# CPU.net
KiCad netlist of a schematic drawn in EAGLE
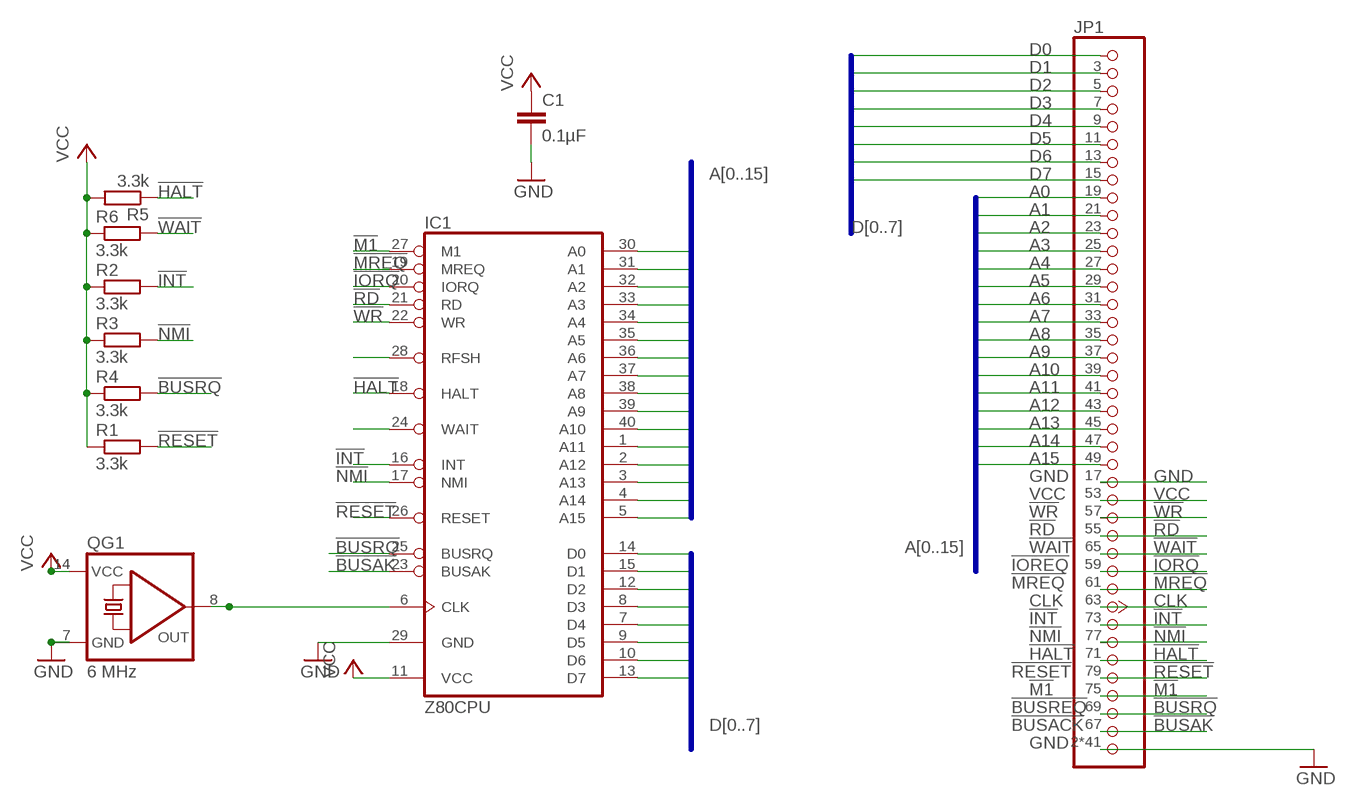
[diagram p0: schematic, sheet 1]

(export (version "E")
  (design (tool "Eeschema 10.0.6"))
  (components
    (comp (ref "C1")
      (value "0.1µF")
      (footprint "eagle-import:C5B2.5")
      (libsource (lib "eagle-import") (part "C5/2.5"))
    )
    (comp (ref "IC1")
      (value "Z80CPU")
      (footprint "eagle-import:DIL40")
      (libsource (lib "eagle-import") (part "Z80CPU"))
    )
    (comp (ref "JP1")
      (value "JEANNECTOR/90")
      (footprint "eagle-import:2X25_90")
      (libsource (lib "eagle-import") (part "JEANNECTOR/90"))
    )
    (comp (ref "QG1")
      (value "6 MHz")
      (footprint "eagle-import:DIL14S")
      (libsource (lib "eagle-import") (part "QG5860"))
    )
    (comp (ref "R1")
      (value "3.3k")
      (footprint "eagle-import:0207_2V")
      (libsource (lib "eagle-import") (part "R-EU_0207/2V"))
    )
    (comp (ref "R2")
      (value "3.3k")
      (footprint "eagle-import:0207_2V")
      (libsource (lib "eagle-import") (part "R-EU_0207/2V"))
    )
    (comp (ref "R3")
      (value "3.3k")
      (footprint "eagle-import:0207_2V")
      (libsource (lib "eagle-import") (part "R-EU_0207/2V"))
    )
    (comp (ref "R4")
      (value "3.3k")
      (footprint "eagle-import:0207_2V")
      (libsource (lib "eagle-import") (part "R-EU_0207/2V"))
    )
    (comp (ref "R5")
      (value "3.3k")
      (footprint "eagle-import:0207_2V")
      (libsource (lib "eagle-import") (part "R-EU_0207/2V"))
    )
    (comp (ref "R6")
      (value "3.3k")
      (footprint "eagle-import:0207_2V")
      (libsource (lib "eagle-import") (part "R-EU_0207/2V"))
    )
  )
  (nets
    (net (code "1") (name "/A0") (class "Default")
      (node (ref "IC1") (pin "30") (pinfunction "A0_30") (pintype "output"))
      (node (ref "JP1") (pin "19") (pinfunction "A0_19") (pintype "bidirectional"))
    )
    (net (code "2") (name "/A1") (class "Default")
      (node (ref "IC1") (pin "31") (pinfunction "A1_31") (pintype "output"))
      (node (ref "JP1") (pin "21") (pinfunction "A1_21") (pintype "bidirectional"))
    )
    (net (code "3") (name "/A2") (class "Default")
      (node (ref "IC1") (pin "32") (pinfunction "A2_32") (pintype "output"))
      (node (ref "JP1") (pin "23") (pinfunction "A2_23") (pintype "bidirectional"))
    )
    (net (code "4") (name "/A3") (class "Default")
      (node (ref "IC1") (pin "33") (pinfunction "A3_33") (pintype "output"))
      (node (ref "JP1") (pin "25") (pinfunction "A3_25") (pintype "bidirectional"))
    )
    (net (code "5") (name "/A4") (class "Default")
      (node (ref "IC1") (pin "34") (pinfunction "A4_34") (pintype "output"))
      (node (ref "JP1") (pin "27") (pinfunction "A4_27") (pintype "bidirectional"))
    )
    (net (code "6") (name "/A5") (class "Default")
      (node (ref "IC1") (pin "35") (pinfunction "A5_35") (pintype "output"))
      (node (ref "JP1") (pin "29") (pinfunction "A5_29") (pintype "bidirectional"))
    )
    (net (code "7") (name "/A6") (class "Default")
      (node (ref "IC1") (pin "36") (pinfunction "A6_36") (pintype "output"))
      (node (ref "JP1") (pin "31") (pinfunction "A6_31") (pintype "bidirectional"))
    )
    (net (code "8") (name "/A7") (class "Default")
      (node (ref "IC1") (pin "37") (pinfunction "A7_37") (pintype "output"))
      (node (ref "JP1") (pin "33") (pinfunction "A7_33") (pintype "bidirectional"))
    )
    (net (code "9") (name "/A8") (class "Default")
      (node (ref "IC1") (pin "38") (pinfunction "A8_38") (pintype "output"))
      (node (ref "JP1") (pin "35") (pinfunction "A8_35") (pintype "bidirectional"))
    )
    (net (code "10") (name "/A9") (class "Default")
      (node (ref "IC1") (pin "39") (pinfunction "A9_39") (pintype "output"))
      (node (ref "JP1") (pin "37") (pinfunction "A9_37") (pintype "bidirectional"))
    )
    (net (code "11") (name "/A10") (class "Default")
      (node (ref "IC1") (pin "40") (pinfunction "A10_40") (pintype "output"))
      (node (ref "JP1") (pin "39") (pinfunction "A10_39") (pintype "bidirectional"))
    )
    (net (code "12") (name "/A11") (class "Default")
      (node (ref "IC1") (pin "1") (pinfunction "A11_1") (pintype "output"))
      (node (ref "JP1") (pin "41") (pinfunction "A11_41") (pintype "bidirectional"))
    )
    (net (code "13") (name "/A12") (class "Default")
      (node (ref "IC1") (pin "2") (pinfunction "A12_2") (pintype "output"))
      (node (ref "JP1") (pin "43") (pinfunction "A12_43") (pintype "bidirectional"))
    )
    (net (code "14") (name "/A13") (class "Default")
      (node (ref "IC1") (pin "3") (pinfunction "A13_3") (pintype "output"))
      (node (ref "JP1") (pin "45") (pinfunction "A13_45") (pintype "bidirectional"))
    )
    (net (code "15") (name "/A14") (class "Default")
      (node (ref "IC1") (pin "4") (pinfunction "A14_4") (pintype "output"))
      (node (ref "JP1") (pin "47") (pinfunction "A14_47") (pintype "bidirectional"))
    )
    (net (code "16") (name "/A15") (class "Default")
      (node (ref "IC1") (pin "5") (pinfunction "A15_5") (pintype "output"))
      (node (ref "JP1") (pin "49") (pinfunction "A15_49") (pintype "bidirectional"))
    )
    (net (code "18") (name "/CLK") (class "Default")
      (node (ref "IC1") (pin "6") (pinfunction "CLK_6") (pintype "input"))
      (node (ref "JP1") (pin "63") (pinfunction "CLK_63") (pintype "passive"))
      (node (ref "QG1") (pin "8") (pinfunction "OUT_8") (pintype "output"))
    )
    (net (code "19") (name "/D0") (class "Default")
      (node (ref "IC1") (pin "14") (pinfunction "D0_14") (pintype "bidirectional"))
      (node (ref "JP1") (pin "1") (pinfunction "D0_1") (pintype "bidirectional"))
    )
    (net (code "20") (name "/D1") (class "Default")
      (node (ref "IC1") (pin "15") (pinfunction "D1_15") (pintype "bidirectional"))
      (node (ref "JP1") (pin "3") (pinfunction "D1_3") (pintype "bidirectional"))
    )
    (net (code "21") (name "/D2") (class "Default")
      (node (ref "IC1") (pin "12") (pinfunction "D2_12") (pintype "bidirectional"))
      (node (ref "JP1") (pin "5") (pinfunction "D2_5") (pintype "bidirectional"))
    )
    (net (code "22") (name "/D3") (class "Default")
      (node (ref "IC1") (pin "8") (pinfunction "D3_8") (pintype "bidirectional"))
      (node (ref "JP1") (pin "7") (pinfunction "D3_7") (pintype "bidirectional"))
    )
    (net (code "23") (name "/D4") (class "Default")
      (node (ref "IC1") (pin "7") (pinfunction "D4_7") (pintype "bidirectional"))
      (node (ref "JP1") (pin "9") (pinfunction "D4_9") (pintype "bidirectional"))
    )
    (net (code "24") (name "/D5") (class "Default")
      (node (ref "IC1") (pin "9") (pinfunction "D5_9") (pintype "bidirectional"))
      (node (ref "JP1") (pin "11") (pinfunction "D5_11") (pintype "bidirectional"))
    )
    (net (code "25") (name "/D6") (class "Default")
      (node (ref "IC1") (pin "10") (pinfunction "D6_10") (pintype "bidirectional"))
      (node (ref "JP1") (pin "13") (pinfunction "D6_13") (pintype "bidirectional"))
    )
    (net (code "26") (name "/D7") (class "Default")
      (node (ref "IC1") (pin "13") (pinfunction "D7_13") (pintype "bidirectional"))
      (node (ref "JP1") (pin "15") (pinfunction "D7_15") (pintype "bidirectional"))
    )
    (net (code "28") (name "/~{BUSAK}") (class "Default")
      (node (ref "IC1") (pin "23") (pinfunction "BUSAK_23") (pintype "output"))
      (node (ref "JP1") (pin "67") (pinfunction "~{BUSACK}_67") (pintype "input"))
    )
    (net (code "29") (name "/~{BUSRQ}") (class "Default")
      (node (ref "IC1") (pin "25") (pinfunction "BUSRQ_25") (pintype "input"))
      (node (ref "JP1") (pin "69") (pinfunction "~{BUSRQ}_69") (pintype "output"))
      (node (ref "R4") (pin "2") (pinfunction "2_2") (pintype "passive"))
    )
    (net (code "30") (name "/~{HALT}") (class "Default")
      (node (ref "IC1") (pin "18") (pinfunction "HALT_18") (pintype "output"))
      (node (ref "JP1") (pin "71") (pinfunction "~{HALT}_71") (pintype "input"))
      (node (ref "R5") (pin "1") (pinfunction "1_1") (pintype "passive"))
    )
    (net (code "31") (name "/~{INT}") (class "Default")
      (node (ref "IC1") (pin "16") (pinfunction "INT_16") (pintype "input"))
      (node (ref "JP1") (pin "73") (pinfunction "~{INT}_73") (pintype "bidirectional"))
      (node (ref "R2") (pin "2") (pinfunction "2_2") (pintype "passive"))
    )
    (net (code "32") (name "/~{IORQ}") (class "Default")
      (node (ref "IC1") (pin "20") (pinfunction "IORQ_20") (pintype "output"))
      (node (ref "JP1") (pin "59") (pinfunction "~{IOREQ}_59") (pintype "output"))
    )
    (net (code "33") (name "/~{M1}") (class "Default")
      (node (ref "IC1") (pin "27") (pinfunction "M1_27") (pintype "output"))
      (node (ref "JP1") (pin "75") (pinfunction "~{M1}_75") (pintype "bidirectional"))
    )
    (net (code "34") (name "/~{MREQ}") (class "Default")
      (node (ref "IC1") (pin "19") (pinfunction "MREQ_19") (pintype "output"))
      (node (ref "JP1") (pin "61") (pinfunction "~{MREQ}_61") (pintype "output"))
    )
    (net (code "35") (name "/~{NMI}") (class "Default")
      (node (ref "IC1") (pin "17") (pinfunction "NMI_17") (pintype "input"))
      (node (ref "JP1") (pin "77") (pinfunction "~{NMI}_77") (pintype "bidirectional"))
      (node (ref "R3") (pin "2") (pinfunction "2_2") (pintype "passive"))
    )
    (net (code "36") (name "/~{RD}") (class "Default")
      (node (ref "IC1") (pin "21") (pinfunction "RD_21") (pintype "output"))
      (node (ref "JP1") (pin "55") (pinfunction "~{RD}_55") (pintype "output"))
    )
    (net (code "37") (name "/~{RESET}") (class "Default")
      (node (ref "IC1") (pin "26") (pinfunction "RESET_26") (pintype "input"))
      (node (ref "JP1") (pin "79") (pinfunction "~{RESET}_79") (pintype "bidirectional"))
      (node (ref "R1") (pin "2") (pinfunction "2_2") (pintype "passive"))
    )
    (net (code "38") (name "/~{WAIT}") (class "Default")
      (node (ref "IC1") (pin "24") (pinfunction "WAIT_24") (pintype "input"))
      (node (ref "JP1") (pin "65") (pinfunction "~{WAIT}_65") (pintype "input"))
      (node (ref "R6") (pin "2") (pinfunction "2_2") (pintype "passive"))
    )
    (net (code "39") (name "/~{WR}") (class "Default")
      (node (ref "IC1") (pin "22") (pinfunction "WR_22") (pintype "output"))
      (node (ref "JP1") (pin "57") (pinfunction "~{WR}_57") (pintype "output"))
    )
    (net (code "40") (name "GND") (class "Default")
      (node (ref "C1") (pin "2") (pinfunction "2_2") (pintype "passive"))
      (node (ref "IC1") (pin "29") (pinfunction "GND_29") (pintype "power_in"))
      (node (ref "JP1") (pin "10") (pinfunction "GND_10") (pintype "power_in"))
      (node (ref "JP1") (pin "12") (pinfunction "GND_12") (pintype "power_in"))
      (node (ref "JP1") (pin "14") (pinfunction "GND_14") (pintype "power_in"))
      (node (ref "JP1") (pin "16") (pinfunction "GND_16") (pintype "power_in"))
      (node (ref "JP1") (pin "17") (pinfunction "GND_17") (pintype "power_in"))
      (node (ref "JP1") (pin "18") (pinfunction "GND_18") (pintype "power_in"))
      (node (ref "JP1") (pin "2") (pinfunction "GND_2") (pintype "power_in"))
      (node (ref "JP1") (pin "20") (pinfunction "GND_20") (pintype "power_in"))
      (node (ref "JP1") (pin "22") (pinfunction "GND_22") (pintype "power_in"))
      (node (ref "JP1") (pin "24") (pinfunction "GND_24") (pintype "power_in"))
      (node (ref "JP1") (pin "26") (pinfunction "GND_26") (pintype "power_in"))
      (node (ref "JP1") (pin "28") (pinfunction "GND_28") (pintype "power_in"))
      (node (ref "JP1") (pin "30") (pinfunction "GND_30") (pintype "power_in"))
      (node (ref "JP1") (pin "32") (pinfunction "GND_32") (pintype "power_in"))
      (node (ref "JP1") (pin "34") (pinfunction "GND_34") (pintype "power_in"))
      (node (ref "JP1") (pin "36") (pinfunction "GND_36") (pintype "power_in"))
      (node (ref "JP1") (pin "38") (pinfunction "GND_38") (pintype "power_in"))
      (node (ref "JP1") (pin "4") (pinfunction "GND_4") (pintype "power_in"))
      (node (ref "JP1") (pin "40") (pinfunction "GND_40") (pintype "power_in"))
      (node (ref "JP1") (pin "42") (pinfunction "GND_42") (pintype "power_in"))
      (node (ref "JP1") (pin "44") (pinfunction "GND_44") (pintype "power_in"))
      (node (ref "JP1") (pin "46") (pinfunction "GND_46") (pintype "power_in"))
      (node (ref "JP1") (pin "48") (pinfunction "GND_48") (pintype "power_in"))
      (node (ref "JP1") (pin "50") (pinfunction "GND_50") (pintype "power_in"))
      (node (ref "JP1") (pin "51") (pinfunction "GND_51") (pintype "power_in"))
      (node (ref "JP1") (pin "52") (pinfunction "GND_52") (pintype "power_in"))
      (node (ref "JP1") (pin "54") (pinfunction "GND_54") (pintype "power_in"))
      (node (ref "JP1") (pin "56") (pinfunction "GND_56") (pintype "power_in"))
      (node (ref "JP1") (pin "58") (pinfunction "GND_58") (pintype "power_in"))
      (node (ref "JP1") (pin "6") (pinfunction "GND_6") (pintype "power_in"))
      (node (ref "JP1") (pin "60") (pinfunction "GND_60") (pintype "power_in"))
      (node (ref "JP1") (pin "62") (pinfunction "GND_62") (pintype "power_in"))
      (node (ref "JP1") (pin "64") (pinfunction "GND_64") (pintype "power_in"))
      (node (ref "JP1") (pin "66") (pinfunction "GND_66") (pintype "power_in"))
      (node (ref "JP1") (pin "68") (pinfunction "GND_68") (pintype "power_in"))
      (node (ref "JP1") (pin "70") (pinfunction "GND_70") (pintype "power_in"))
      (node (ref "JP1") (pin "72") (pinfunction "GND_72") (pintype "power_in"))
      (node (ref "JP1") (pin "74") (pinfunction "GND_74") (pintype "power_in"))
      (node (ref "JP1") (pin "76") (pinfunction "GND_76") (pintype "power_in"))
      (node (ref "JP1") (pin "78") (pinfunction "GND_78") (pintype "power_in"))
      (node (ref "JP1") (pin "8") (pinfunction "GND_8") (pintype "power_in"))
      (node (ref "JP1") (pin "80") (pinfunction "GND_80") (pintype "power_in"))
      (node (ref "QG1") (pin "7") (pinfunction "GND_7") (pintype "power_in"))
    )
    (net (code "41") (name "VCC") (class "Default")
      (node (ref "C1") (pin "1") (pinfunction "1_1") (pintype "passive"))
      (node (ref "IC1") (pin "11") (pinfunction "VCC_11") (pintype "power_in"))
      (node (ref "JP1") (pin "53") (pinfunction "VCC_53") (pintype "power_in"))
      (node (ref "QG1") (pin "14") (pinfunction "VCC_14") (pintype "power_in"))
      (node (ref "R1") (pin "1") (pinfunction "1_1") (pintype "passive"))
      (node (ref "R2") (pin "1") (pinfunction "1_1") (pintype "passive"))
      (node (ref "R3") (pin "1") (pinfunction "1_1") (pintype "passive"))
      (node (ref "R4") (pin "1") (pinfunction "1_1") (pintype "passive"))
      (node (ref "R5") (pin "2") (pinfunction "2_2") (pintype "passive"))
      (node (ref "R6") (pin "1") (pinfunction "1_1") (pintype "passive"))
    )
    (net (code "42") (name "unconnected-(IC1-RFSH-Pad28)") (class "Default")
      (node (ref "IC1") (pin "28") (pinfunction "RFSH_28") (pintype "output"))
    )
  )
)
